# 468323_001_LED_DRV_TEC.net
KiCad netlist of a schematic drawn in Altium Designer
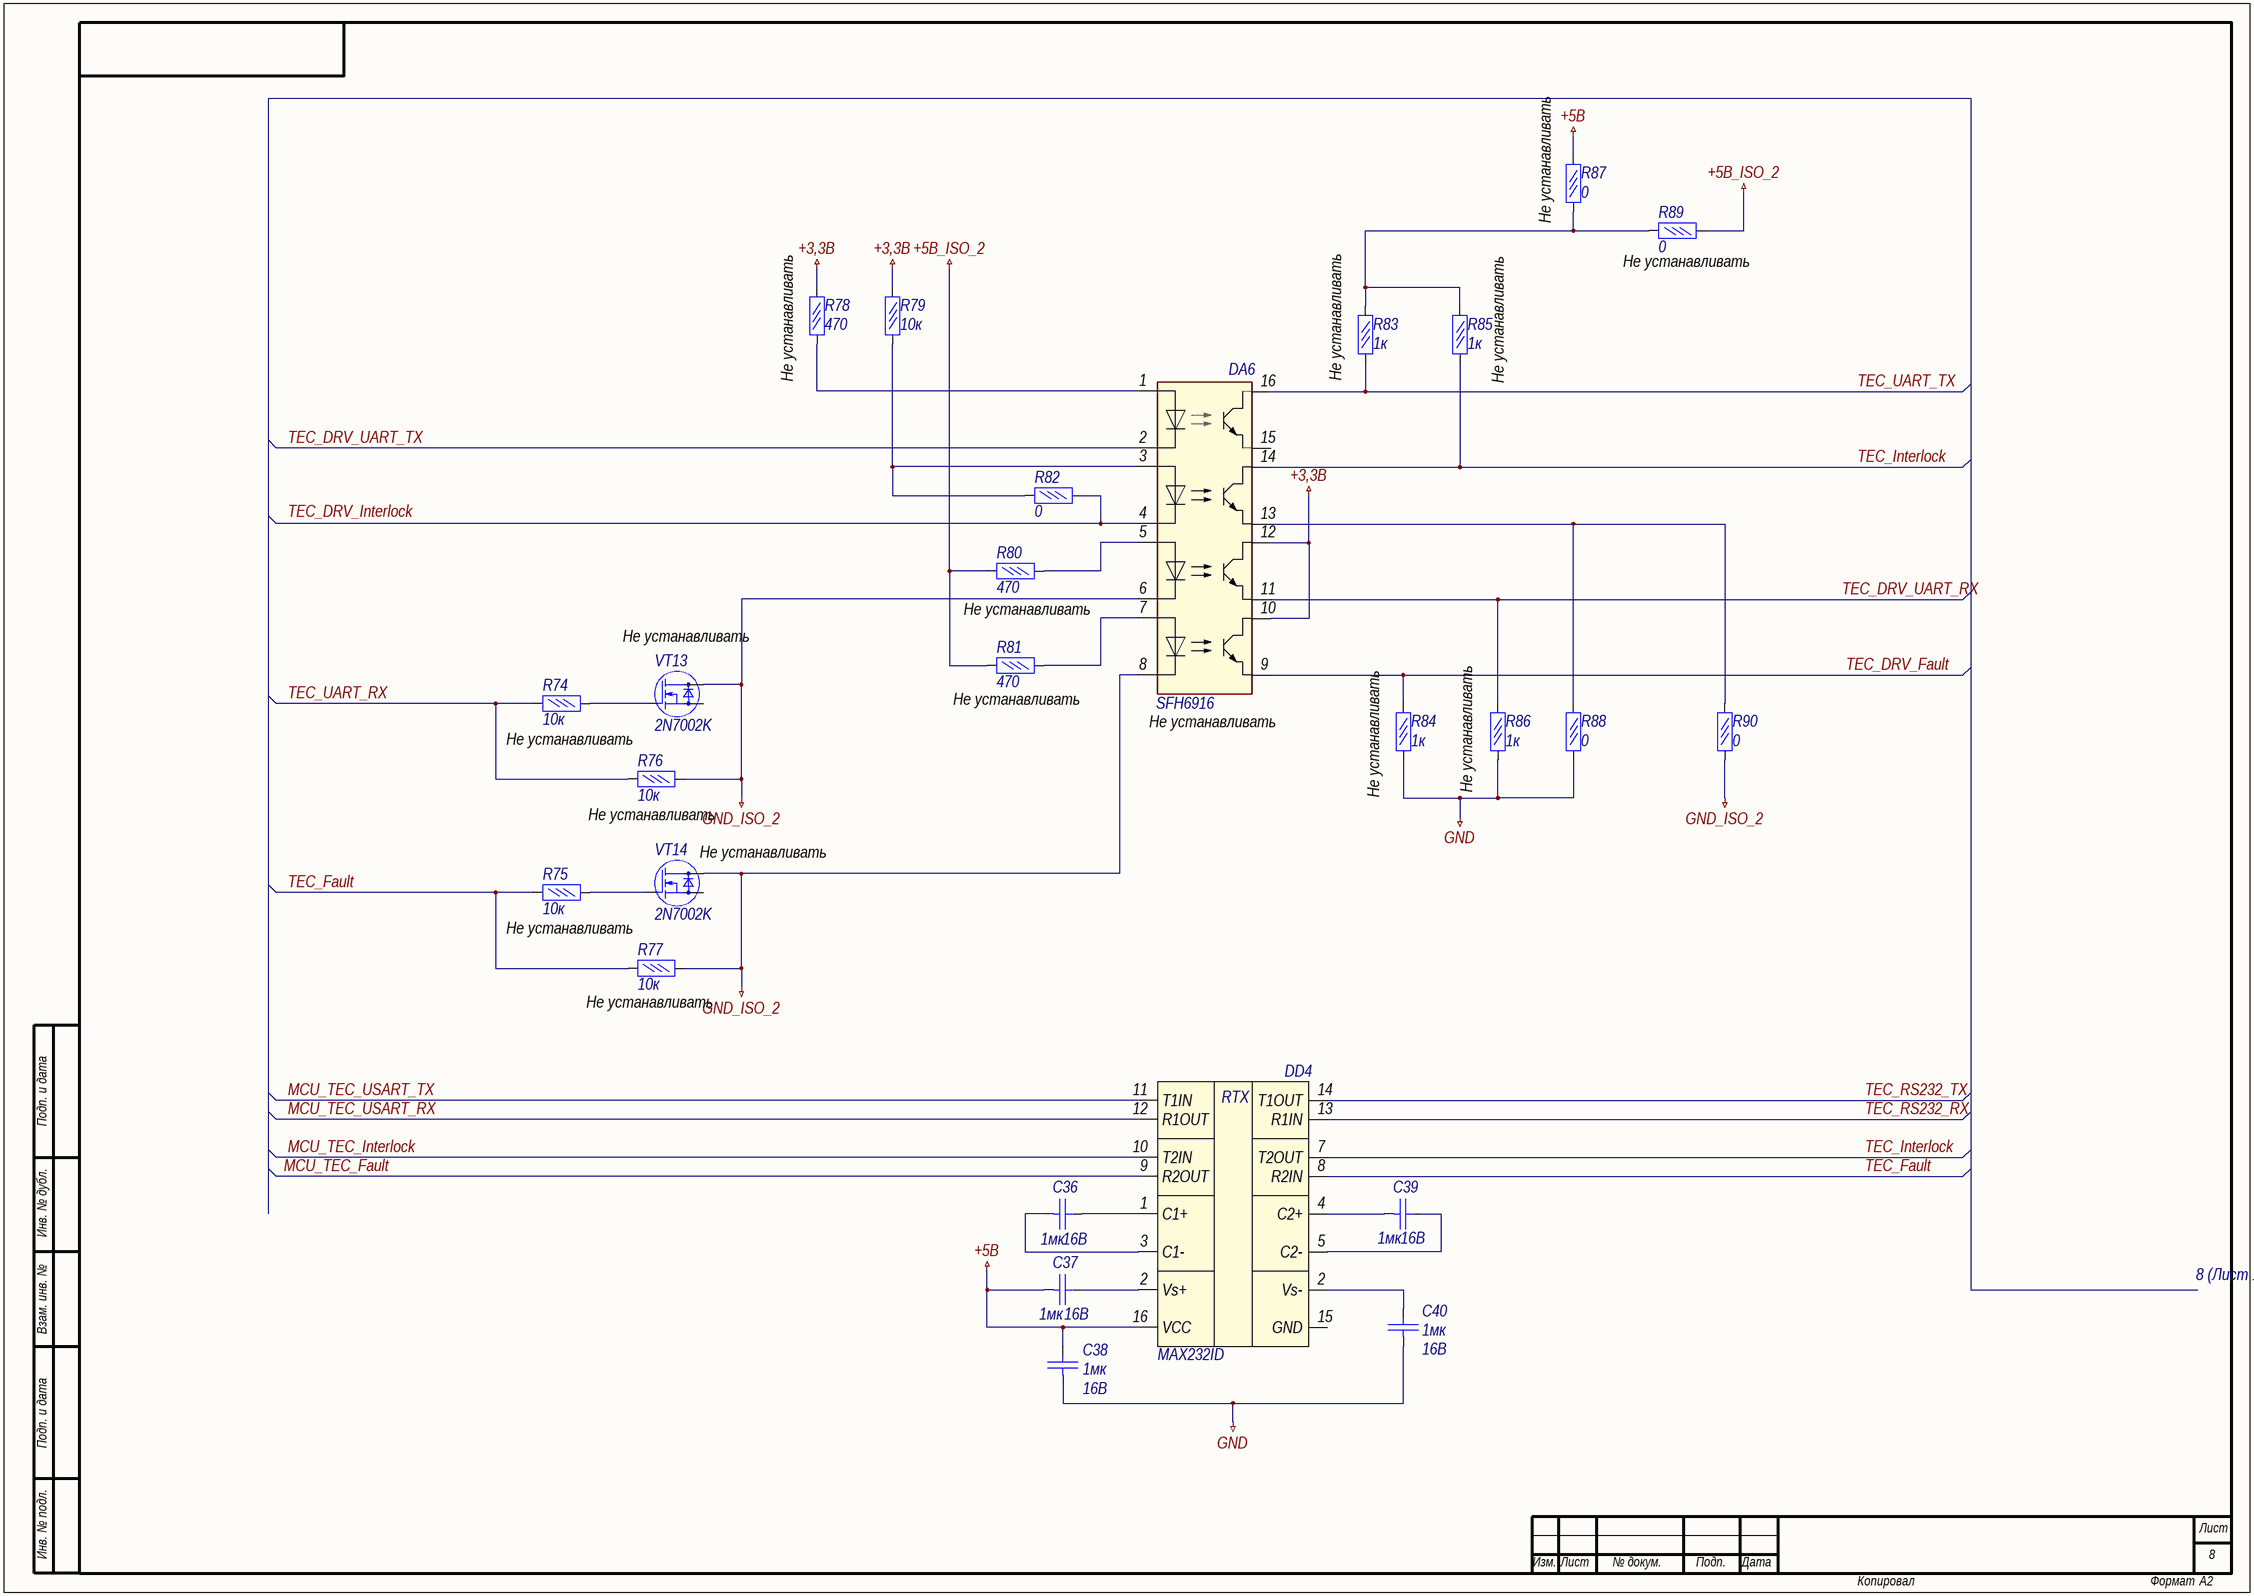
[diagram p0: РЕУН.468323.001_LED_DRV_TEC.SchDoc]

(export (version "E")
  (design (tool "Eeschema 10.0.6"))
  (components
    (comp (ref "C36")
      (value "1мк")
      (footprint "C0805_AA")
      (description "Конденсатор кер.")
      (fields (field (name "VOLTAGE") "16В"))
      (libsource (lib "Library_Diana") (part "Конденсатор кер."))
    )
    (comp (ref "C37")
      (value "1мк")
      (footprint "C0805_AA")
      (description "Конденсатор кер.")
      (fields (field (name "VOLTAGE") "16В"))
      (libsource (lib "Library_Diana") (part "Конденсатор кер."))
    )
    (comp (ref "C38")
      (value "1мк")
      (footprint "C0805_AA")
      (description "Конденсатор кер.")
      (fields (field (name "VOLTAGE") "16В"))
      (libsource (lib "Library_Diana") (part "Конденсатор кер."))
    )
    (comp (ref "C39")
      (value "1мк")
      (footprint "C0805_AA")
      (description "Конденсатор кер.")
      (fields (field (name "VOLTAGE") "16В"))
      (libsource (lib "Library_Diana") (part "Конденсатор кер."))
    )
    (comp (ref "C40")
      (value "1мк")
      (footprint "C0805_AA")
      (description "Конденсатор кер.")
      (fields (field (name "VOLTAGE") "16В"))
      (libsource (lib "Library_Diana") (part "Конденсатор кер."))
    )
    (comp (ref "DA6")
      (value "SFH6916")
      (description "Опторазвязка х4")
      (libsource (lib "Library_Diana") (part "OPTO-4"))
    )
    (comp (ref "DD4")
      (value "MAX232ID")
      (description "Dual EIA-232 Drivers/Receivers")
      (libsource (lib "Library_Diana") (part "MAX232ID"))
    )
    (comp (ref "R74")
      (value "10к")
      (footprint "R1206")
      (description "Резистор 0,05Вт")
      (libsource (lib "Library_Diana") (part "Резистор  0,05Вт"))
    )
    (comp (ref "R75")
      (value "10к")
      (footprint "R1206")
      (description "Резистор 0,05Вт")
      (libsource (lib "Library_Diana") (part "Резистор  0,05Вт"))
    )
    (comp (ref "R76")
      (value "10к")
      (footprint "R1206")
      (description "Резистор 0,05Вт")
      (libsource (lib "Library_Diana") (part "Резистор  0,05Вт"))
    )
    (comp (ref "R77")
      (value "10к")
      (footprint "R1206")
      (description "Резистор 0,05Вт")
      (libsource (lib "Library_Diana") (part "Резистор  0,05Вт"))
    )
    (comp (ref "R78")
      (value "470")
      (footprint "R1206")
      (description "Резистор 0,05Вт")
      (libsource (lib "") (part "Резистор  0,05Вт_2"))
    )
    (comp (ref "R79")
      (value "10к")
      (footprint "R1206")
      (description "Резистор 0,05Вт")
      (libsource (lib "") (part "Резистор  0,05Вт_1"))
    )
    (comp (ref "R80")
      (value "470")
      (footprint "R1206")
      (description "Резистор 0,05Вт")
      (libsource (lib "Library_Diana") (part "Резистор  0,05Вт"))
    )
    (comp (ref "R81")
      (value "470")
      (footprint "R1206")
      (description "Резистор 0,05Вт")
      (libsource (lib "Library_Diana") (part "Резистор  0,05Вт"))
    )
    (comp (ref "R82")
      (value "0")
      (footprint "R1206")
      (description "Резистор 0,05Вт")
      (libsource (lib "Library_Diana") (part "Резистор  0,05Вт"))
    )
    (comp (ref "R83")
      (value "1к")
      (footprint "R1206")
      (description "Резистор 0,05Вт")
      (libsource (lib "") (part "Резистор  0,05Вт_1"))
    )
    (comp (ref "R84")
      (value "1к")
      (footprint "R1206")
      (description "Резистор 0,05Вт")
      (libsource (lib "") (part "Резистор  0,05Вт_1"))
    )
    (comp (ref "R85")
      (value "1к")
      (footprint "R1206")
      (description "Резистор 0,05Вт")
      (libsource (lib "") (part "Резистор  0,05Вт_1"))
    )
    (comp (ref "R86")
      (value "1к")
      (footprint "R1206")
      (description "Резистор 0,05Вт")
      (libsource (lib "") (part "Резистор  0,05Вт_1"))
    )
    (comp (ref "R87")
      (value "0")
      (footprint "R1206")
      (description "Резистор 0,05Вт")
      (libsource (lib "") (part "Резистор  0,05Вт_2"))
    )
    (comp (ref "R88")
      (value "0")
      (footprint "R1206")
      (description "Резистор 0,05Вт")
      (libsource (lib "") (part "Резистор  0,05Вт_1"))
    )
    (comp (ref "R89")
      (value "0")
      (footprint "R1206")
      (description "Резистор 0,05Вт")
      (libsource (lib "") (part "Резистор  0,05Вт_3"))
    )
    (comp (ref "R90")
      (value "0")
      (footprint "R1206")
      (description "Резистор 0,05Вт")
      (libsource (lib "") (part "Резистор  0,05Вт_1"))
    )
    (comp (ref "VT13")
      (value "2N7002K")
      (footprint "SOT:SOT23-3")
      (fields (field (name "NAME") "2N7002K"))
      (libsource (lib "Library_Diana") (part "mosfet-n"))
    )
    (comp (ref "VT14")
      (value "2N7002K")
      (footprint "SOT:SOT23-3")
      (fields (field (name "NAME") "2N7002K"))
      (libsource (lib "Library_Diana") (part "mosfet-n"))
    )
  )
  (nets
    (net (code "1") (name "+3,3В") (class "Default")
      (node (ref "DA6") (pin "10") (pintype "passive"))
      (node (ref "DA6") (pin "12") (pintype "passive"))
      (node (ref "R78") (pin "1") (pinfunction "1_1") (pintype "passive"))
      (node (ref "R79") (pin "2") (pinfunction "2_2") (pintype "passive"))
    )
    (net (code "2") (name "+5В") (class "Default")
      (node (ref "C37") (pin "2") (pinfunction "2_2") (pintype "passive"))
      (node (ref "C38") (pin "1") (pinfunction "1_1") (pintype "passive"))
      (node (ref "DD4") (pin "16") (pinfunction "VCC_16") (pintype "passive"))
      (node (ref "R87") (pin "1") (pinfunction "1_1") (pintype "passive"))
    )
    (net (code "3") (name "+5В_ISO_2") (class "Default")
      (node (ref "R80") (pin "1") (pinfunction "1_1") (pintype "passive"))
      (node (ref "R81") (pin "1") (pinfunction "1_1") (pintype "passive"))
      (node (ref "R89") (pin "1") (pinfunction "1_1") (pintype "passive"))
    )
    (net (code "4") (name "/MCU_TEC_Fault") (class "Default")
      (node (ref "DD4") (pin "9") (pinfunction "R2OUT_9") (pintype "passive"))
    )
    (net (code "5") (name "/MCU_TEC_Interlock") (class "Default")
      (node (ref "DD4") (pin "10") (pinfunction "T2IN_10") (pintype "passive"))
    )
    (net (code "6") (name "/MCU_TEC_USART_RX") (class "Default")
      (node (ref "DD4") (pin "12") (pinfunction "R1OUT_12") (pintype "passive"))
    )
    (net (code "7") (name "/MCU_TEC_USART_TX") (class "Default")
      (node (ref "DD4") (pin "11") (pinfunction "T1IN_11") (pintype "passive"))
    )
    (net (code "8") (name "/TEC_DRV_Fault") (class "Default")
      (node (ref "DA6") (pin "9") (pintype "passive"))
      (node (ref "R84") (pin "2") (pinfunction "2_2") (pintype "passive"))
    )
    (net (code "10") (name "/TEC_DRV_UART_RX") (class "Default")
      (node (ref "DA6") (pin "11") (pintype "passive"))
      (node (ref "R86") (pin "2") (pinfunction "2_2") (pintype "passive"))
    )
    (net (code "11") (name "/TEC_DRV_UART_TX") (class "Default")
      (node (ref "DA6") (pin "2") (pintype "passive"))
    )
    (net (code "12") (name "/TEC_Fault") (class "Default")
      (node (ref "DD4") (pin "8") (pinfunction "R2IN_8") (pintype "passive"))
      (node (ref "R75") (pin "1") (pinfunction "1_1") (pintype "passive"))
      (node (ref "R77") (pin "1") (pinfunction "1_1") (pintype "passive"))
    )
    (net (code "13") (name "/TEC_Interlock") (class "Default")
      (node (ref "DA6") (pin "14") (pintype "passive"))
      (node (ref "DD4") (pin "7") (pinfunction "T2OUT_7") (pintype "passive"))
      (node (ref "R85") (pin "1") (pinfunction "1_1") (pintype "passive"))
    )
    (net (code "14") (name "/TEC_RS232_RX") (class "Default")
      (node (ref "DD4") (pin "13") (pinfunction "R1IN_13") (pintype "passive"))
    )
    (net (code "15") (name "/TEC_RS232_TX") (class "Default")
      (node (ref "DD4") (pin "14") (pinfunction "T1OUT_14") (pintype "passive"))
    )
    (net (code "16") (name "/TEC_UART_RX") (class "Default")
      (node (ref "R74") (pin "1") (pinfunction "1_1") (pintype "passive"))
      (node (ref "R76") (pin "1") (pinfunction "1_1") (pintype "passive"))
    )
    (net (code "17") (name "/TEC_UART_TX") (class "Default")
      (node (ref "DA6") (pin "16") (pintype "passive"))
      (node (ref "R83") (pin "1") (pinfunction "1_1") (pintype "passive"))
    )
    (net (code "18") (name "GND") (class "Default")
      (node (ref "C38") (pin "2") (pinfunction "2_2") (pintype "passive"))
      (node (ref "C40") (pin "2") (pinfunction "2_2") (pintype "passive"))
      (node (ref "R84") (pin "1") (pinfunction "1_1") (pintype "passive"))
      (node (ref "R86") (pin "1") (pinfunction "1_1") (pintype "passive"))
      (node (ref "R88") (pin "1") (pinfunction "1_1") (pintype "passive"))
    )
    (net (code "19") (name "GND_ISO_2") (class "Default")
      (node (ref "DA6") (pin "6") (pintype "passive"))
      (node (ref "DA6") (pin "8") (pintype "passive"))
      (node (ref "R76") (pin "2") (pinfunction "2_2") (pintype "passive"))
      (node (ref "R77") (pin "2") (pinfunction "2_2") (pintype "passive"))
      (node (ref "R90") (pin "1") (pinfunction "1_1") (pintype "passive"))
      (node (ref "VT13") (pin "3") (pinfunction "D_3") (pintype "passive"))
      (node (ref "VT14") (pin "3") (pinfunction "D_3") (pintype "passive"))
    )
    (net (code "20") (name "Net-(DA6-Pad1)") (class "Default")
      (node (ref "DA6") (pin "1") (pintype "passive"))
      (node (ref "R78") (pin "2") (pinfunction "2_2") (pintype "passive"))
    )
    (net (code "21") (name "Net-(DA6-Pad3)") (class "Default")
      (node (ref "DA6") (pin "3") (pintype "passive"))
      (node (ref "R79") (pin "1") (pinfunction "1_1") (pintype "passive"))
      (node (ref "R82") (pin "1") (pinfunction "1_1") (pintype "passive"))
    )
    (net (code "22") (name "Net-(DA6-Pad4)") (class "Default")
      (node (ref "DA6") (pin "4") (pintype "passive"))
      (node (ref "R82") (pin "2") (pinfunction "2_2") (pintype "passive"))
    )
    (net (code "23") (name "Net-(DA6-Pad5)") (class "Default")
      (node (ref "DA6") (pin "5") (pintype "passive"))
      (node (ref "R80") (pin "2") (pinfunction "2_2") (pintype "passive"))
    )
    (net (code "24") (name "Net-(DA6-Pad7)") (class "Default")
      (node (ref "DA6") (pin "7") (pintype "passive"))
      (node (ref "R81") (pin "2") (pinfunction "2_2") (pintype "passive"))
    )
    (net (code "25") (name "Net-(DA6-Pad13)") (class "Default")
      (node (ref "DA6") (pin "13") (pintype "passive"))
      (node (ref "R88") (pin "2") (pinfunction "2_2") (pintype "passive"))
      (node (ref "R90") (pin "2") (pinfunction "2_2") (pintype "passive"))
    )
    (net (code "26") (name "Net-(DD4-C1+)") (class "Default")
      (node (ref "C36") (pin "1") (pinfunction "1_1") (pintype "passive"))
      (node (ref "DD4") (pin "1") (pinfunction "C1+_1") (pintype "passive"))
    )
    (net (code "27") (name "Net-(DD4-C1-)") (class "Default")
      (node (ref "C36") (pin "2") (pinfunction "2_2") (pintype "passive"))
      (node (ref "DD4") (pin "3") (pinfunction "C1-_3") (pintype "passive"))
    )
    (net (code "28") (name "Net-(DD4-C2+)") (class "Default")
      (node (ref "C39") (pin "2") (pinfunction "2_2") (pintype "passive"))
      (node (ref "DD4") (pin "4") (pinfunction "C2+_4") (pintype "passive"))
    )
    (net (code "29") (name "Net-(DD4-C2-)") (class "Default")
      (node (ref "C39") (pin "1") (pinfunction "1_1") (pintype "passive"))
      (node (ref "DD4") (pin "5") (pinfunction "C2-_5") (pintype "passive"))
    )
    (net (code "30") (name "Net-(DD4-Vs+)") (class "Default")
      (node (ref "C37") (pin "1") (pinfunction "1_1") (pintype "passive"))
      (node (ref "DD4") (pin "2") (pinfunction "Vs+_2") (pintype "passive"))
    )
    (net (code "31") (name "Net-(DD4-Vs-)") (class "Default")
      (node (ref "C40") (pin "1") (pinfunction "1_1") (pintype "passive"))
      (node (ref "DD4") (pin "2") (pinfunction "Vs-_2") (pintype "passive"))
    )
    (net (code "32") (name "Net-(R83-Pad2)") (class "Default")
      (node (ref "R83") (pin "2") (pinfunction "2_2") (pintype "passive"))
      (node (ref "R85") (pin "2") (pinfunction "2_2") (pintype "passive"))
      (node (ref "R87") (pin "2") (pinfunction "2_2") (pintype "passive"))
      (node (ref "R89") (pin "2") (pinfunction "2_2") (pintype "passive"))
    )
    (net (code "33") (name "Net-(VT13-G)") (class "Default")
      (node (ref "R74") (pin "2") (pinfunction "2_2") (pintype "passive"))
      (node (ref "VT13") (pin "1") (pinfunction "G_1") (pintype "passive"))
    )
    (net (code "34") (name "Net-(VT14-G)") (class "Default")
      (node (ref "R75") (pin "2") (pinfunction "2_2") (pintype "passive"))
      (node (ref "VT14") (pin "1") (pinfunction "G_1") (pintype "passive"))
    )
    (net (code "35") (name "unconnected-(DA6-Pad15)") (class "Default")
      (node (ref "DA6") (pin "15") (pintype "passive"))
    )
    (net (code "36") (name "unconnected-(DD4-GND-Pad15)") (class "Default")
      (node (ref "DD4") (pin "15") (pinfunction "GND_15") (pintype "passive"))
    )
    (net (code "37") (name "unconnected-(VT13-S-Pad2)") (class "Default")
      (node (ref "VT13") (pin "2") (pinfunction "S_2") (pintype "passive"))
    )
    (net (code "38") (name "unconnected-(VT14-S-Pad2)") (class "Default")
      (node (ref "VT14") (pin "2") (pinfunction "S_2") (pintype "passive"))
    )
  )
)
